# Scarab_v03.net
KiCad netlist of a schematic drawn in EAGLE
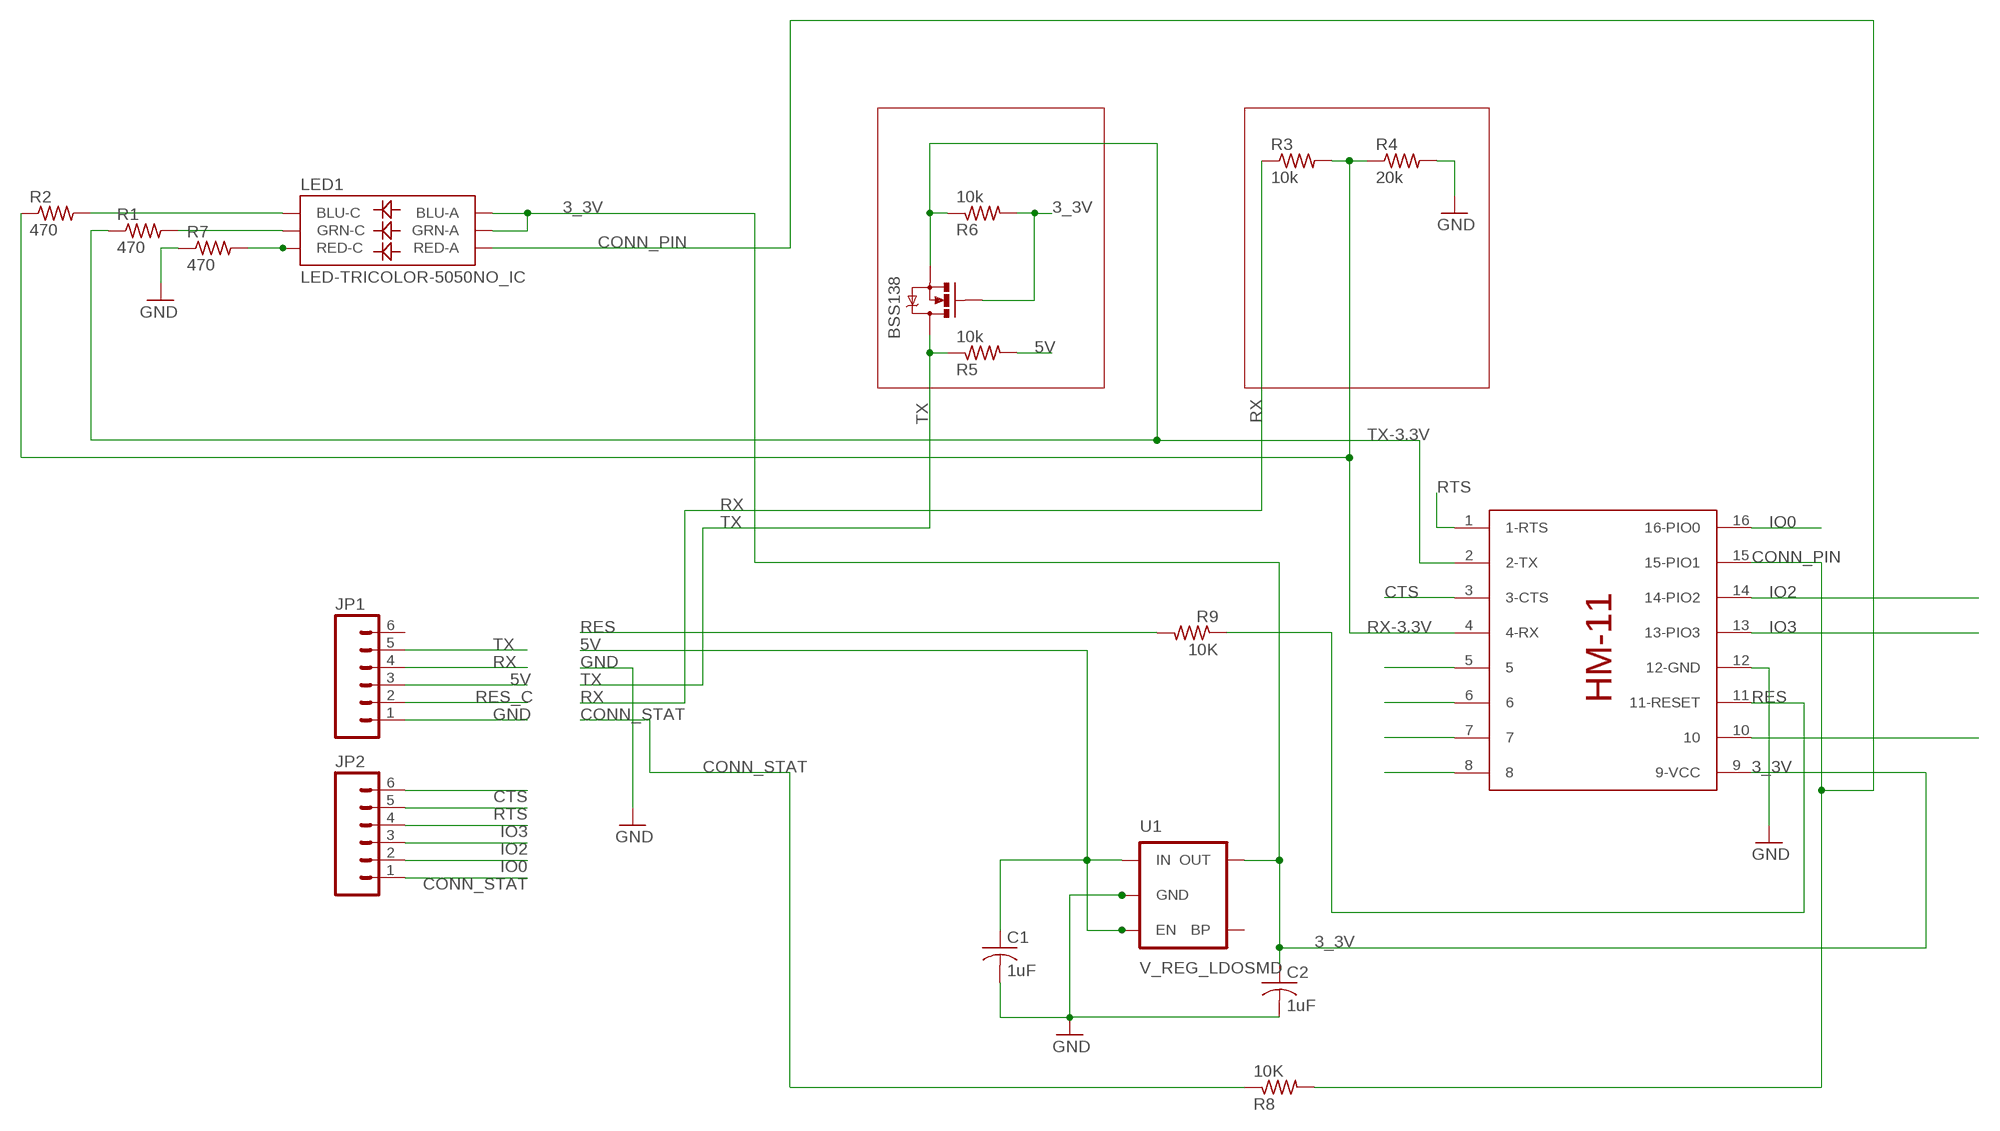
[diagram p0: schematic, sheet 1]

(export (version "E")
  (design (tool "Eeschema 10.0.6"))
  (components
    (comp (ref "BSS138")
      (value "MOSFET-NCHANNELSMD")
      (footprint "eagle-import:SOT23-3")
      (libsource (lib "eagle-import") (part "MOSFET-NCHANNELSMD"))
    )
    (comp (ref "C1")
      (value "1uF")
      (footprint "eagle-import:C0402")
      (libsource (lib "eagle-import") (part "C-USC0402"))
    )
    (comp (ref "C2")
      (value "1uF")
      (footprint "eagle-import:C0402")
      (libsource (lib "eagle-import") (part "C-USC0402"))
    )
    (comp (ref "JP1")
      (value "M06LOCK")
      (footprint "eagle-import:1X06_LOCK")
      (libsource (lib "eagle-import") (part "M06LOCK"))
    )
    (comp (ref "JP2")
      (value "M06LOCK")
      (footprint "eagle-import:1X06_LOCK")
      (libsource (lib "eagle-import") (part "M06LOCK"))
    )
    (comp (ref "LED1")
      (value "LED-TRICOLOR-5050NO_IC")
      (footprint "eagle-import:LED-TRICOLOR-5050")
      (libsource (lib "eagle-import") (part "LED-TRICOLOR-5050NO_IC"))
    )
    (comp (ref "R1")
      (value "470")
      (footprint "eagle-import:R0402")
      (libsource (lib "eagle-import") (part "R-US_R0402"))
    )
    (comp (ref "R2")
      (value "470")
      (footprint "eagle-import:R0402")
      (libsource (lib "eagle-import") (part "R-US_R0402"))
    )
    (comp (ref "R3")
      (value "10k")
      (footprint "eagle-import:R0402")
      (libsource (lib "eagle-import") (part "R-US_R0402"))
    )
    (comp (ref "R4")
      (value "20k")
      (footprint "eagle-import:R0402")
      (libsource (lib "eagle-import") (part "R-US_R0402"))
    )
    (comp (ref "R5")
      (value "10k")
      (footprint "eagle-import:R0402")
      (libsource (lib "eagle-import") (part "R-US_R0402"))
    )
    (comp (ref "R6")
      (value "10k")
      (footprint "eagle-import:R0402")
      (libsource (lib "eagle-import") (part "R-US_R0402"))
    )
    (comp (ref "R7")
      (value "470")
      (footprint "eagle-import:R0402")
      (libsource (lib "eagle-import") (part "R-US_R0402"))
    )
    (comp (ref "R8")
      (value "10K")
      (footprint "eagle-import:R0402")
      (libsource (lib "eagle-import") (part "R-US_R0402"))
    )
    (comp (ref "R9")
      (value "10K")
      (footprint "eagle-import:R0402")
      (libsource (lib "eagle-import") (part "R-US_R0402"))
    )
    (comp (ref "U$1")
      (value "HM-11")
      (footprint "eagle-import:HM-11")
      (libsource (lib "eagle-import") (part "HM-11"))
    )
    (comp (ref "U1")
      (value "V_REG_LDOSMD")
      (footprint "eagle-import:SOT23-5")
      (libsource (lib "eagle-import") (part "V_REG_LDOSMD"))
    )
  )
  (nets
    (net (code "1") (name "/3_3V") (class "Default")
      (node (ref "BSS138") (pin "1") (pinfunction "G_1") (pintype "passive"))
      (node (ref "C2") (pin "1") (pinfunction "1_1") (pintype "passive"))
      (node (ref "LED1") (pin "1") (pinfunction "GRN-A_1") (pintype "bidirectional"))
      (node (ref "LED1") (pin "3") (pinfunction "BLU-A_3") (pintype "bidirectional"))
      (node (ref "R6") (pin "2") (pinfunction "2_2") (pintype "passive"))
      (node (ref "U$1") (pin "9") (pinfunction "9-VCC_9") (pintype "bidirectional"))
      (node (ref "U1") (pin "5") (pinfunction "OUT_5") (pintype "passive"))
    )
    (net (code "2") (name "/5V") (class "Default")
      (node (ref "C1") (pin "1") (pinfunction "1_1") (pintype "passive"))
      (node (ref "JP1") (pin "3") (pinfunction "3_3") (pintype "passive"))
      (node (ref "R5") (pin "2") (pinfunction "2_2") (pintype "passive"))
      (node (ref "U1") (pin "1") (pinfunction "IN_1") (pintype "input"))
      (node (ref "U1") (pin "3") (pinfunction "EN_3") (pintype "input"))
    )
    (net (code "3") (name "/CONN_PIN") (class "Default")
      (node (ref "LED1") (pin "2") (pinfunction "RED-A_2") (pintype "bidirectional"))
      (node (ref "R8") (pin "2") (pinfunction "2_2") (pintype "passive"))
      (node (ref "U$1") (pin "15") (pinfunction "15-PIO1_15") (pintype "bidirectional"))
    )
    (net (code "4") (name "/CONN_STAT") (class "Default")
      (node (ref "JP2") (pin "1") (pinfunction "1_1") (pintype "passive"))
      (node (ref "R8") (pin "1") (pinfunction "1_1") (pintype "passive"))
    )
    (net (code "5") (name "/CTS") (class "Default")
      (node (ref "JP2") (pin "6") (pinfunction "6_6") (pintype "passive"))
      (node (ref "U$1") (pin "3") (pinfunction "3-CTS_3") (pintype "bidirectional"))
    )
    (net (code "6") (name "/IO0") (class "Default")
      (node (ref "JP2") (pin "2") (pinfunction "2_2") (pintype "passive"))
      (node (ref "U$1") (pin "16") (pinfunction "16-PIO0_16") (pintype "bidirectional"))
    )
    (net (code "7") (name "/IO2") (class "Default")
      (node (ref "JP2") (pin "3") (pinfunction "3_3") (pintype "passive"))
      (node (ref "U$1") (pin "14") (pinfunction "14-PIO2_14") (pintype "bidirectional"))
    )
    (net (code "8") (name "/IO3") (class "Default")
      (node (ref "JP2") (pin "4") (pinfunction "4_4") (pintype "passive"))
      (node (ref "U$1") (pin "13") (pinfunction "13-PIO3_13") (pintype "bidirectional"))
    )
    (net (code "9") (name "/RES") (class "Default")
      (node (ref "R9") (pin "1") (pinfunction "1_1") (pintype "passive"))
      (node (ref "U$1") (pin "11") (pinfunction "11-RESET_11") (pintype "bidirectional"))
    )
    (net (code "10") (name "/RES_C") (class "Default")
      (node (ref "JP1") (pin "2") (pinfunction "2_2") (pintype "passive"))
      (node (ref "R9") (pin "2") (pinfunction "2_2") (pintype "passive"))
    )
    (net (code "11") (name "/RTS") (class "Default")
      (node (ref "JP2") (pin "5") (pinfunction "5_5") (pintype "passive"))
      (node (ref "U$1") (pin "1") (pinfunction "1-RTS_1") (pintype "bidirectional"))
    )
    (net (code "12") (name "/RX") (class "Default")
      (node (ref "JP1") (pin "4") (pinfunction "4_4") (pintype "passive"))
      (node (ref "R3") (pin "1") (pinfunction "1_1") (pintype "passive"))
    )
    (net (code "13") (name "/RX-3.3V") (class "Default")
      (node (ref "R2") (pin "1") (pinfunction "1_1") (pintype "passive"))
      (node (ref "R3") (pin "2") (pinfunction "2_2") (pintype "passive"))
      (node (ref "R4") (pin "1") (pinfunction "1_1") (pintype "passive"))
      (node (ref "U$1") (pin "4") (pinfunction "4-RX_4") (pintype "bidirectional"))
    )
    (net (code "14") (name "/TX") (class "Default")
      (node (ref "BSS138") (pin "3") (pinfunction "D_3") (pintype "passive"))
      (node (ref "JP1") (pin "5") (pinfunction "5_5") (pintype "passive"))
      (node (ref "R5") (pin "1") (pinfunction "1_1") (pintype "passive"))
    )
    (net (code "15") (name "/TX-3.3V") (class "Default")
      (node (ref "BSS138") (pin "2") (pinfunction "S_2") (pintype "passive"))
      (node (ref "R1") (pin "1") (pinfunction "1_1") (pintype "passive"))
      (node (ref "R6") (pin "1") (pinfunction "1_1") (pintype "passive"))
      (node (ref "U$1") (pin "2") (pinfunction "2-TX_2") (pintype "bidirectional"))
    )
    (net (code "16") (name "GND") (class "Default")
      (node (ref "C1") (pin "2") (pinfunction "2_2") (pintype "passive"))
      (node (ref "C2") (pin "2") (pinfunction "2_2") (pintype "passive"))
      (node (ref "JP1") (pin "1") (pinfunction "1_1") (pintype "passive"))
      (node (ref "R4") (pin "2") (pinfunction "2_2") (pintype "passive"))
      (node (ref "R7") (pin "1") (pinfunction "1_1") (pintype "passive"))
      (node (ref "U$1") (pin "12") (pinfunction "12-GND_12") (pintype "bidirectional"))
      (node (ref "U1") (pin "2") (pinfunction "GND_2") (pintype "input"))
    )
    (net (code "17") (name "Net-(LED1-BLU-C)") (class "Default")
      (node (ref "LED1") (pin "4") (pinfunction "BLU-C_4") (pintype "bidirectional"))
      (node (ref "R2") (pin "2") (pinfunction "2_2") (pintype "passive"))
    )
    (net (code "18") (name "Net-(LED1-GRN-C)") (class "Default")
      (node (ref "LED1") (pin "6") (pinfunction "GRN-C_6") (pintype "bidirectional"))
      (node (ref "R1") (pin "2") (pinfunction "2_2") (pintype "passive"))
    )
    (net (code "19") (name "Net-(LED1-RED-C)") (class "Default")
      (node (ref "LED1") (pin "5") (pinfunction "RED-C_5") (pintype "bidirectional"))
      (node (ref "R7") (pin "2") (pinfunction "2_2") (pintype "passive"))
    )
    (net (code "20") (name "unconnected-(JP1-Pad6)") (class "Default")
      (node (ref "JP1") (pin "6") (pinfunction "6_6") (pintype "passive"))
    )
    (net (code "21") (name "unconnected-(U$1-Pad5)") (class "Default")
      (node (ref "U$1") (pin "5") (pinfunction "5_5") (pintype "bidirectional"))
    )
    (net (code "22") (name "unconnected-(U$1-Pad6)") (class "Default")
      (node (ref "U$1") (pin "6") (pinfunction "6_6") (pintype "bidirectional"))
    )
    (net (code "23") (name "unconnected-(U$1-Pad7)") (class "Default")
      (node (ref "U$1") (pin "7") (pinfunction "7_7") (pintype "bidirectional"))
    )
    (net (code "24") (name "unconnected-(U$1-Pad8)") (class "Default")
      (node (ref "U$1") (pin "8") (pinfunction "8_8") (pintype "bidirectional"))
    )
    (net (code "25") (name "unconnected-(U$1-Pad10)") (class "Default")
      (node (ref "U$1") (pin "10") (pinfunction "10_10") (pintype "bidirectional"))
    )
    (net (code "26") (name "unconnected-(U1-BP-Pad4)") (class "Default")
      (node (ref "U1") (pin "4") (pinfunction "BP_4") (pintype "input"))
    )
  )
)
